# lighthouse-lantern-v01.net
KiCad netlist of a schematic drawn in EAGLE
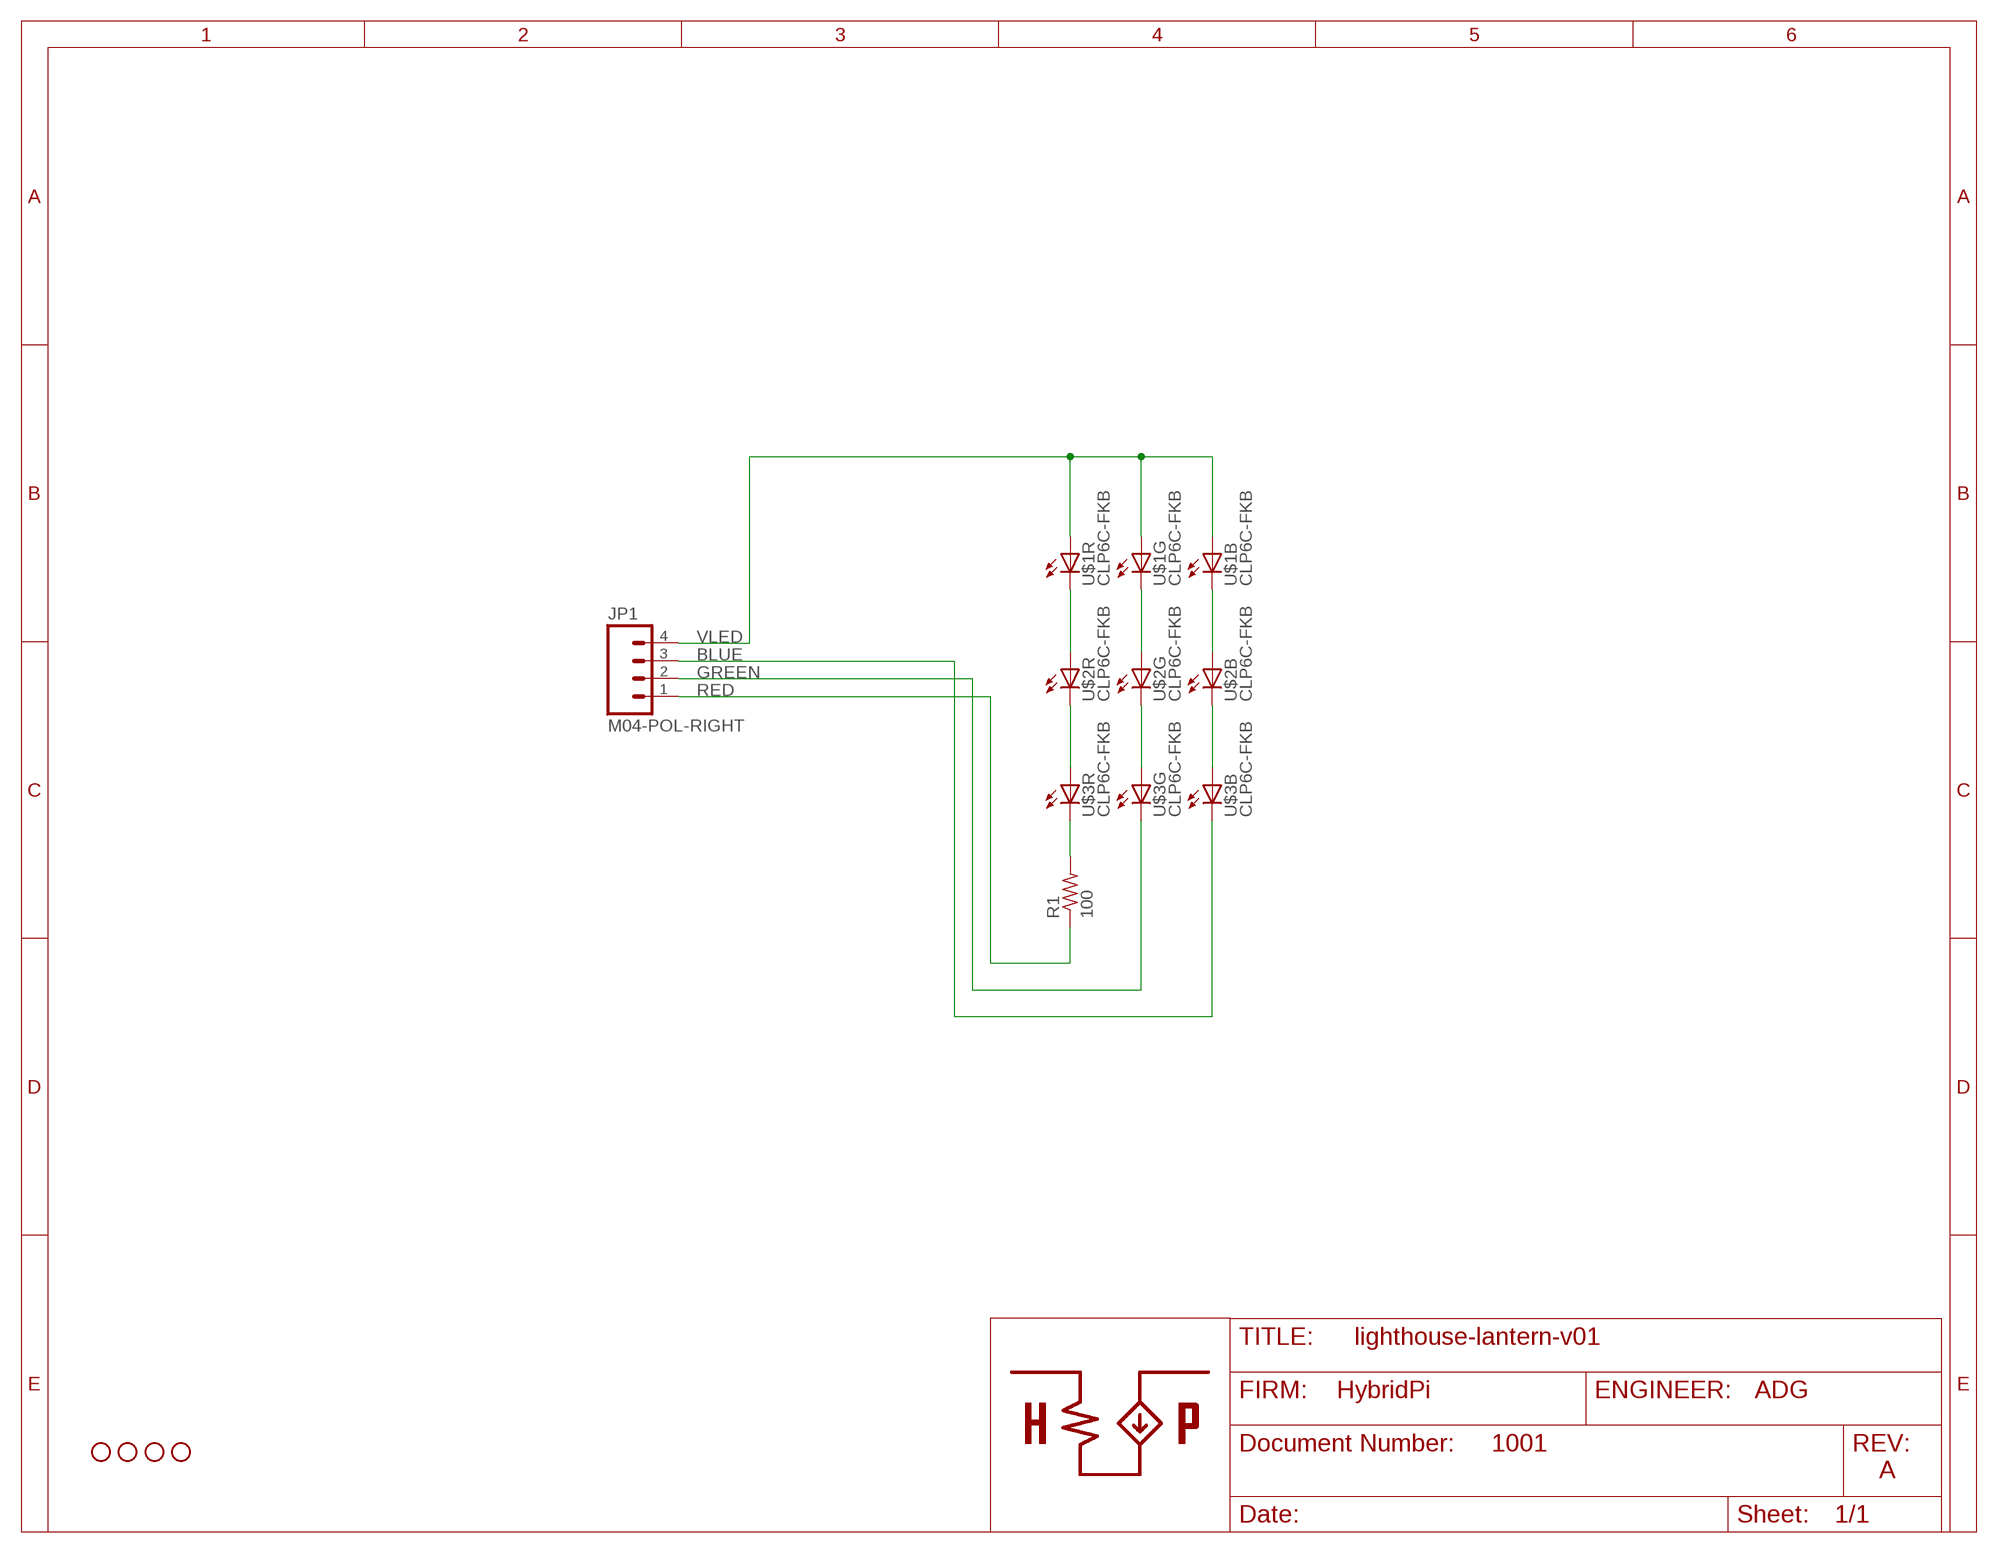
[diagram p0: schematic, sheet 1]

(export (version "E")
  (design (tool "Eeschema 10.0.6"))
  (components
    (comp (ref "JP1")
      (value "M04-POL-RIGHT")
      (footprint "eagle-import:640455-4")
      (libsource (lib "eagle-import") (part "M04-POL-RIGHT"))
    )
    (comp (ref "JP2")
      (value "STAND-OFF")
      (footprint "eagle-import:STAND-OFF")
      (libsource (lib "eagle-import") (part "STAND-OFF"))
    )
    (comp (ref "JP3")
      (value "STAND-OFF")
      (footprint "eagle-import:STAND-OFF")
      (libsource (lib "eagle-import") (part "STAND-OFF"))
    )
    (comp (ref "JP4")
      (value "STAND-OFF")
      (footprint "eagle-import:STAND-OFF")
      (libsource (lib "eagle-import") (part "STAND-OFF"))
    )
    (comp (ref "JP5")
      (value "STAND-OFF")
      (footprint "eagle-import:STAND-OFF")
      (libsource (lib "eagle-import") (part "STAND-OFF"))
    )
    (comp (ref "R1")
      (value "100")
      (footprint "eagle-import:R1206")
      (libsource (lib "eagle-import") (part "R-US_R1206"))
    )
    (comp (ref "U$1")
      (value "CLP6C-FKB")
      (footprint "eagle-import:CLP6C-FKB")
      (libsource (lib "eagle-import") (part "CLP6C-FKB"))
    )
    (comp (ref "U$2")
      (value "CLP6C-FKB")
      (footprint "eagle-import:CLP6C-FKB")
      (libsource (lib "eagle-import") (part "CLP6C-FKB"))
    )
    (comp (ref "U$3")
      (value "CLP6C-FKB")
      (footprint "eagle-import:CLP6C-FKB")
      (libsource (lib "eagle-import") (part "CLP6C-FKB"))
    )
  )
  (nets
    (net (code "1") (name "/BLUE") (class "Default")
      (node (ref "JP1") (pin "3") (pinfunction "3_3") (pintype "passive"))
      (node (ref "U$3") (pin "4") (pinfunction "C_4") (pintype "passive"))
    )
    (net (code "2") (name "/GREEN") (class "Default")
      (node (ref "JP1") (pin "2") (pinfunction "2_2") (pintype "passive"))
      (node (ref "U$3") (pin "5") (pinfunction "C_5") (pintype "passive"))
    )
    (net (code "3") (name "/RED") (class "Default")
      (node (ref "JP1") (pin "1") (pinfunction "1_1") (pintype "passive"))
      (node (ref "R1") (pin "1") (pinfunction "1_1") (pintype "passive"))
    )
    (net (code "4") (name "/VLED") (class "Default")
      (node (ref "JP1") (pin "4") (pinfunction "4_4") (pintype "passive"))
      (node (ref "U$1") (pin "1") (pinfunction "A_1") (pintype "passive"))
      (node (ref "U$1") (pin "2") (pinfunction "A_2") (pintype "passive"))
      (node (ref "U$1") (pin "3") (pinfunction "A_3") (pintype "passive"))
    )
    (net (code "5") (name "Net-(U$1A-C)") (class "Default")
      (node (ref "U$1") (pin "4") (pinfunction "C_4") (pintype "passive"))
      (node (ref "U$2") (pin "3") (pinfunction "A_3") (pintype "passive"))
    )
    (net (code "6") (name "Net-(U$1B-C)") (class "Default")
      (node (ref "U$1") (pin "5") (pinfunction "C_5") (pintype "passive"))
      (node (ref "U$2") (pin "2") (pinfunction "A_2") (pintype "passive"))
    )
    (net (code "7") (name "Net-(U$1C-C)") (class "Default")
      (node (ref "U$1") (pin "6") (pinfunction "C_6") (pintype "passive"))
      (node (ref "U$2") (pin "1") (pinfunction "A_1") (pintype "passive"))
    )
    (net (code "8") (name "Net-(U$2A-C)") (class "Default")
      (node (ref "U$2") (pin "4") (pinfunction "C_4") (pintype "passive"))
      (node (ref "U$3") (pin "3") (pinfunction "A_3") (pintype "passive"))
    )
    (net (code "9") (name "Net-(U$2B-C)") (class "Default")
      (node (ref "U$2") (pin "5") (pinfunction "C_5") (pintype "passive"))
      (node (ref "U$3") (pin "2") (pinfunction "A_2") (pintype "passive"))
    )
    (net (code "10") (name "Net-(U$2C-C)") (class "Default")
      (node (ref "U$2") (pin "6") (pinfunction "C_6") (pintype "passive"))
      (node (ref "U$3") (pin "1") (pinfunction "A_1") (pintype "passive"))
    )
    (net (code "11") (name "Net-(U$3C-C)") (class "Default")
      (node (ref "R1") (pin "2") (pinfunction "2_2") (pintype "passive"))
      (node (ref "U$3") (pin "6") (pinfunction "C_6") (pintype "passive"))
    )
  )
)
